# FTDI.net
KiCad netlist of a schematic drawn in Altium Designer
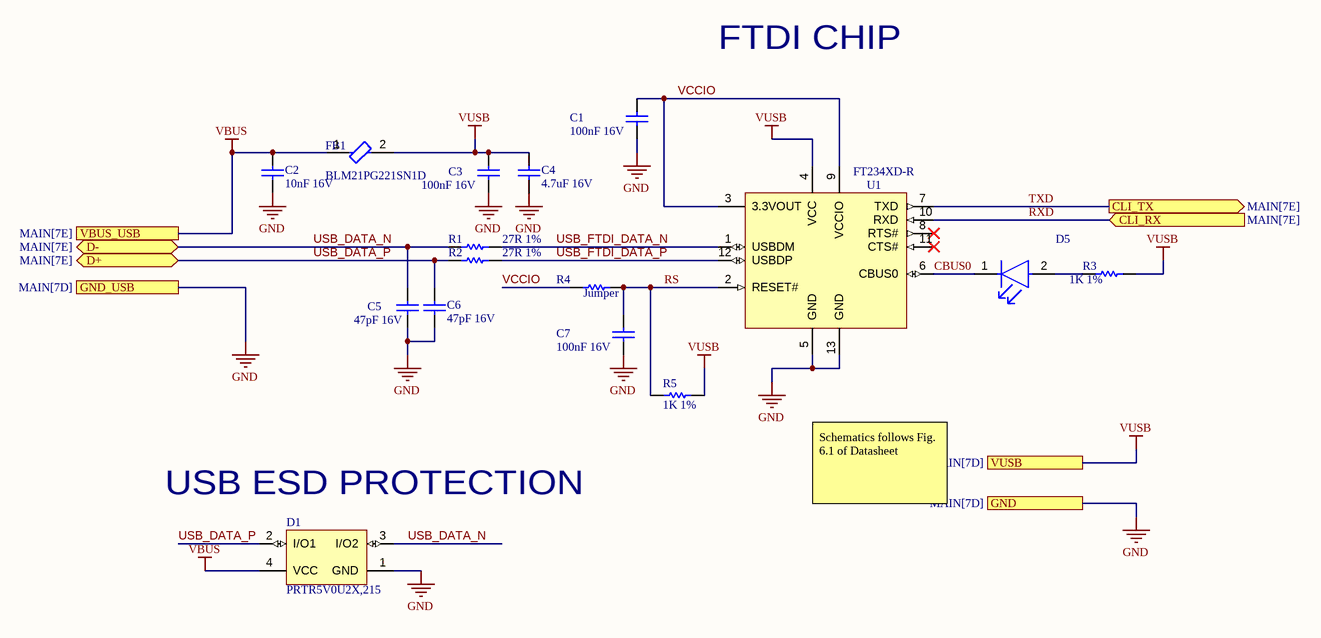
[diagram p0: FTDI.SchDoc]

(export (version "E")
  (design (tool "Eeschema 10.0.6"))
  (components
    (comp (ref "C1")
      (value "100nF 16V")
      (footprint "CAPC1608X95X40NL15T15")
      (fields (field (name "MANUFACTURER") "Vitramon") (field (name "PART NUMBER") "VJ0603Y104KXJCW1BC"))
      (libsource (lib "Altium Content Vault") (part "CAP"))
    )
    (comp (ref "C2")
      (value "10nF 16V")
      (footprint "CAPC1608X87X35ML15T15")
      (fields (field (name "PART NUMBER") "C0603C103K4RACTU") (field (name "MANUFACTURER") "Kemet"))
      (libsource (lib "Altium Content Vault") (part "CAP"))
    )
    (comp (ref "C3")
      (value "100nF 16V")
      (footprint "CAPC1608X95X40NL15T15")
      (fields (field (name "MANUFACTURER") "Vitramon") (field (name "PART NUMBER") "VJ0603Y104KXJCW1BC"))
      (libsource (lib "Altium Content Vault") (part "CAP"))
    )
    (comp (ref "C4")
      (value "4.7uF 16V")
      (footprint "CAPC0805(2012)145_N")
      (description "CAP 4.7uF 16V -20% to +80% 0805 (2012 Metric) Thickness 1.45mm SMD")
      (fields (field (name "TOLERANCE") "-20% to +80%"))
      (libsource (lib "Altium Content Vault") (part "CAP"))
    )
    (comp (ref "C5")
      (value "47pF 16V")
      (footprint "CAPC0603(1608)100_N")
      (description "CAP 47pF 16V ±0.5pF 0603 (1608 Metric) Thickness 1mm SMD")
      (fields (field (name "TOLERANCE") "Â±0.5pF"))
      (libsource (lib "Altium Content Vault") (part "CAP"))
    )
    (comp (ref "C6")
      (value "47pF 16V")
      (footprint "CAPC0603(1608)100_N")
      (description "CAP 47pF 16V ±0.5pF 0603 (1608 Metric) Thickness 1mm SMD")
      (fields (field (name "TOLERANCE") "Â±0.5pF"))
      (libsource (lib "Altium Content Vault") (part "CAP"))
    )
    (comp (ref "C7")
      (value "100nF 16V")
      (footprint "CAPC1608X95X40NL15T15")
      (fields (field (name "MANUFACTURER") "Vitramon") (field (name "PART NUMBER") "VJ0603Y104KXJCW1BC"))
      (libsource (lib "Altium Content Vault") (part "CAP"))
    )
    (comp (ref "D1")
      (value "PRTR5V0U2X,215")
      (footprint "NXP-SOT143B-4_V")
      (fields (field (name "MANUFACTURER") "NXP Semiconductors"))
      (libsource (lib "Altium Content Vault") (part "NXP-PRTR5V0U2X,215-4"))
    )
    (comp (ref "D5")
      (value "LTST-C170CKT")
      (footprint "FP-LTST-C170CKT-MFG")
      (description "LED RED CLEAR SMD")
      (fields (field (name "VOLTAGE") "5V"))
      (libsource (lib "Altium Content Vault") (part "8706943c75ba83719d021d2fdc84c58"))
    )
    (comp (ref "FB1")
      (value "BLM21PG221SN1D")
      (footprint "FP-BLM21-0_2-t0_85-e0_5-IPC_B")
      (description "Chip Ferrite Bead, 0805, 220Ω @ 100MHz, 0.045Ω, 25%, 2A")
      (fields (field (name "TOLERANCE") "25%"))
      (libsource (lib "Altium Content Vault") (part "5f30dd21d616792df468990f7003faa"))
    )
    (comp (ref "R1")
      (value "27R 1%")
      (footprint "RESC0603(1608)_N")
      (description "27R 0.1W 1% 0603 (1608 Metric)  SMD")
      (fields (field (name "TOLERANCE") "1 %") (field (name "POWER") "0.1 W"))
      (libsource (lib "Altium Content Vault") (part "RES"))
    )
    (comp (ref "R2")
      (value "27R 1%")
      (footprint "RESC0603(1608)_N")
      (description "27R 0.1W 1% 0603 (1608 Metric)  SMD")
      (fields (field (name "TOLERANCE") "1 %") (field (name "POWER") "0.1 W"))
      (libsource (lib "Altium Content Vault") (part "RES"))
    )
    (comp (ref "R3")
      (value "1K 1%")
      (footprint "RESC1609X50X30NL10T20")
      (fields (field (name "MANUFACTURER") "Vishay Dale") (field (name "PART NUMBER") "CRCW06031K00FKEB"))
      (libsource (lib "Altium Content Vault") (part "RES"))
    )
    (comp (ref "R4")
      (value "Jumper")
      (footprint "RESC1609X50X30LL10T20")
      (fields (field (name "MANUFACTURER") "Vishay Dale") (field (name "PART NUMBER") "CRCW06030000Z0EC"))
      (libsource (lib "Altium Content Vault") (part "RES"))
    )
    (comp (ref "R5")
      (value "1K 1%")
      (footprint "RESC1609X50X30NL10T20")
      (fields (field (name "MANUFACTURER") "Vishay Dale") (field (name "PART NUMBER") "CRCW06031K00FKEB"))
      (libsource (lib "Altium Content Vault") (part "RES"))
    )
    (comp (ref "U1")
      (value "FT234XD-R")
      (footprint "DFN-12_V")
      (description "FT234XD USB to BASIC UART IC, -40 to +85 degC, 12-Pin DFN, Pb-Free, Tape and Reel")
      (fields (field (name "MANUFACTURER") "FTDI"))
      (libsource (lib "Altium Content Vault") (part "FTDI-FT234XD-DFN-12"))
    )
  )
  (nets
    (net (code "1") (name "/CBUS0") (class "Default")
      (node (ref "D5") (pin "1") (pinfunction "C_1") (pintype "passive"))
      (node (ref "U1") (pin "6") (pinfunction "CBUS0_6") (pintype "bidirectional"))
    )
    (net (code "2") (name "/RS") (class "Default")
      (node (ref "C7") (pin "2") (pinfunction "2_2") (pintype "passive"))
      (node (ref "R4") (pin "2") (pinfunction "2_2") (pintype "passive"))
      (node (ref "R5") (pin "2") (pinfunction "2_2") (pintype "passive"))
      (node (ref "U1") (pin "2") (pinfunction "RESET#_2") (pintype "input"))
    )
    (net (code "3") (name "/RXD") (class "Default")
      (node (ref "U1") (pin "10") (pinfunction "RXD_10") (pintype "input"))
    )
    (net (code "4") (name "/TXD") (class "Default")
      (node (ref "U1") (pin "7") (pinfunction "TXD_7") (pintype "output"))
    )
    (net (code "5") (name "/USB_DATA_N") (class "Default")
      (node (ref "C5") (pin "2") (pinfunction "2_2") (pintype "passive"))
      (node (ref "D1") (pin "3") (pinfunction "I/O2_3") (pintype "bidirectional"))
      (node (ref "R1") (pin "1") (pinfunction "1_1") (pintype "passive"))
    )
    (net (code "6") (name "/USB_DATA_P") (class "Default")
      (node (ref "C6") (pin "2") (pinfunction "2_2") (pintype "passive"))
      (node (ref "D1") (pin "2") (pinfunction "I/O1_2") (pintype "bidirectional"))
      (node (ref "R2") (pin "1") (pinfunction "1_1") (pintype "passive"))
    )
    (net (code "7") (name "/USB_FTDI_DATA_N") (class "Default")
      (node (ref "R1") (pin "2") (pinfunction "2_2") (pintype "passive"))
      (node (ref "U1") (pin "1") (pinfunction "USBDM_1") (pintype "bidirectional"))
    )
    (net (code "8") (name "/USB_FTDI_DATA_P") (class "Default")
      (node (ref "R2") (pin "2") (pinfunction "2_2") (pintype "passive"))
      (node (ref "U1") (pin "12") (pinfunction "USBDP_12") (pintype "bidirectional"))
    )
    (net (code "9") (name "/VCCIO") (class "Default")
      (node (ref "C1") (pin "2") (pinfunction "2_2") (pintype "passive"))
      (node (ref "R4") (pin "1") (pinfunction "1_1") (pintype "passive"))
      (node (ref "U1") (pin "3") (pinfunction "3.3VOUT_3") (pintype "power_in"))
      (node (ref "U1") (pin "9") (pinfunction "VCCIO_9") (pintype "power_in"))
    )
    (net (code "10") (name "GND") (class "Default")
      (node (ref "C1") (pin "1") (pinfunction "1_1") (pintype "passive"))
      (node (ref "C2") (pin "1") (pinfunction "1_1") (pintype "passive"))
      (node (ref "C3") (pin "1") (pinfunction "1_1") (pintype "passive"))
      (node (ref "C4") (pin "1") (pinfunction "1_1") (pintype "passive"))
      (node (ref "C5") (pin "1") (pinfunction "1_1") (pintype "passive"))
      (node (ref "C6") (pin "1") (pinfunction "1_1") (pintype "passive"))
      (node (ref "C7") (pin "1") (pinfunction "1_1") (pintype "passive"))
      (node (ref "D1") (pin "1") (pinfunction "GND_1") (pintype "power_in"))
      (node (ref "U1") (pin "13") (pinfunction "GND_13") (pintype "power_in"))
      (node (ref "U1") (pin "5") (pinfunction "GND_5") (pintype "power_in"))
    )
    (net (code "11") (name "Net-(D5-A)") (class "Default")
      (node (ref "D5") (pin "2") (pinfunction "A_2") (pintype "passive"))
      (node (ref "R3") (pin "1") (pinfunction "1_1") (pintype "passive"))
    )
    (net (code "12") (name "VBUS") (class "Default")
      (node (ref "C2") (pin "2") (pinfunction "2_2") (pintype "passive"))
      (node (ref "D1") (pin "4") (pinfunction "VCC_4") (pintype "power_in"))
      (node (ref "FB1") (pin "1") (pinfunction "1_1") (pintype "passive"))
    )
    (net (code "13") (name "VUSB") (class "Default")
      (node (ref "C3") (pin "2") (pinfunction "2_2") (pintype "passive"))
      (node (ref "C4") (pin "2") (pinfunction "2_2") (pintype "passive"))
      (node (ref "FB1") (pin "2") (pinfunction "2_2") (pintype "passive"))
      (node (ref "R3") (pin "2") (pinfunction "2_2") (pintype "passive"))
      (node (ref "R5") (pin "1") (pinfunction "1_1") (pintype "passive"))
      (node (ref "U1") (pin "4") (pinfunction "VCC_4") (pintype "power_in"))
    )
    (net (code "14") (name "unconnected-(U1-CTS#-Pad11)") (class "Default")
      (node (ref "U1") (pin "11") (pinfunction "CTS#_11") (pintype "input+no_connect"))
    )
    (net (code "15") (name "unconnected-(U1-RTS#-Pad8)") (class "Default")
      (node (ref "U1") (pin "8") (pinfunction "RTS#_8") (pintype "output+no_connect"))
    )
  )
)
